# Tension-Logger_Rev_A.net
KiCad netlist of a schematic drawn in EAGLE
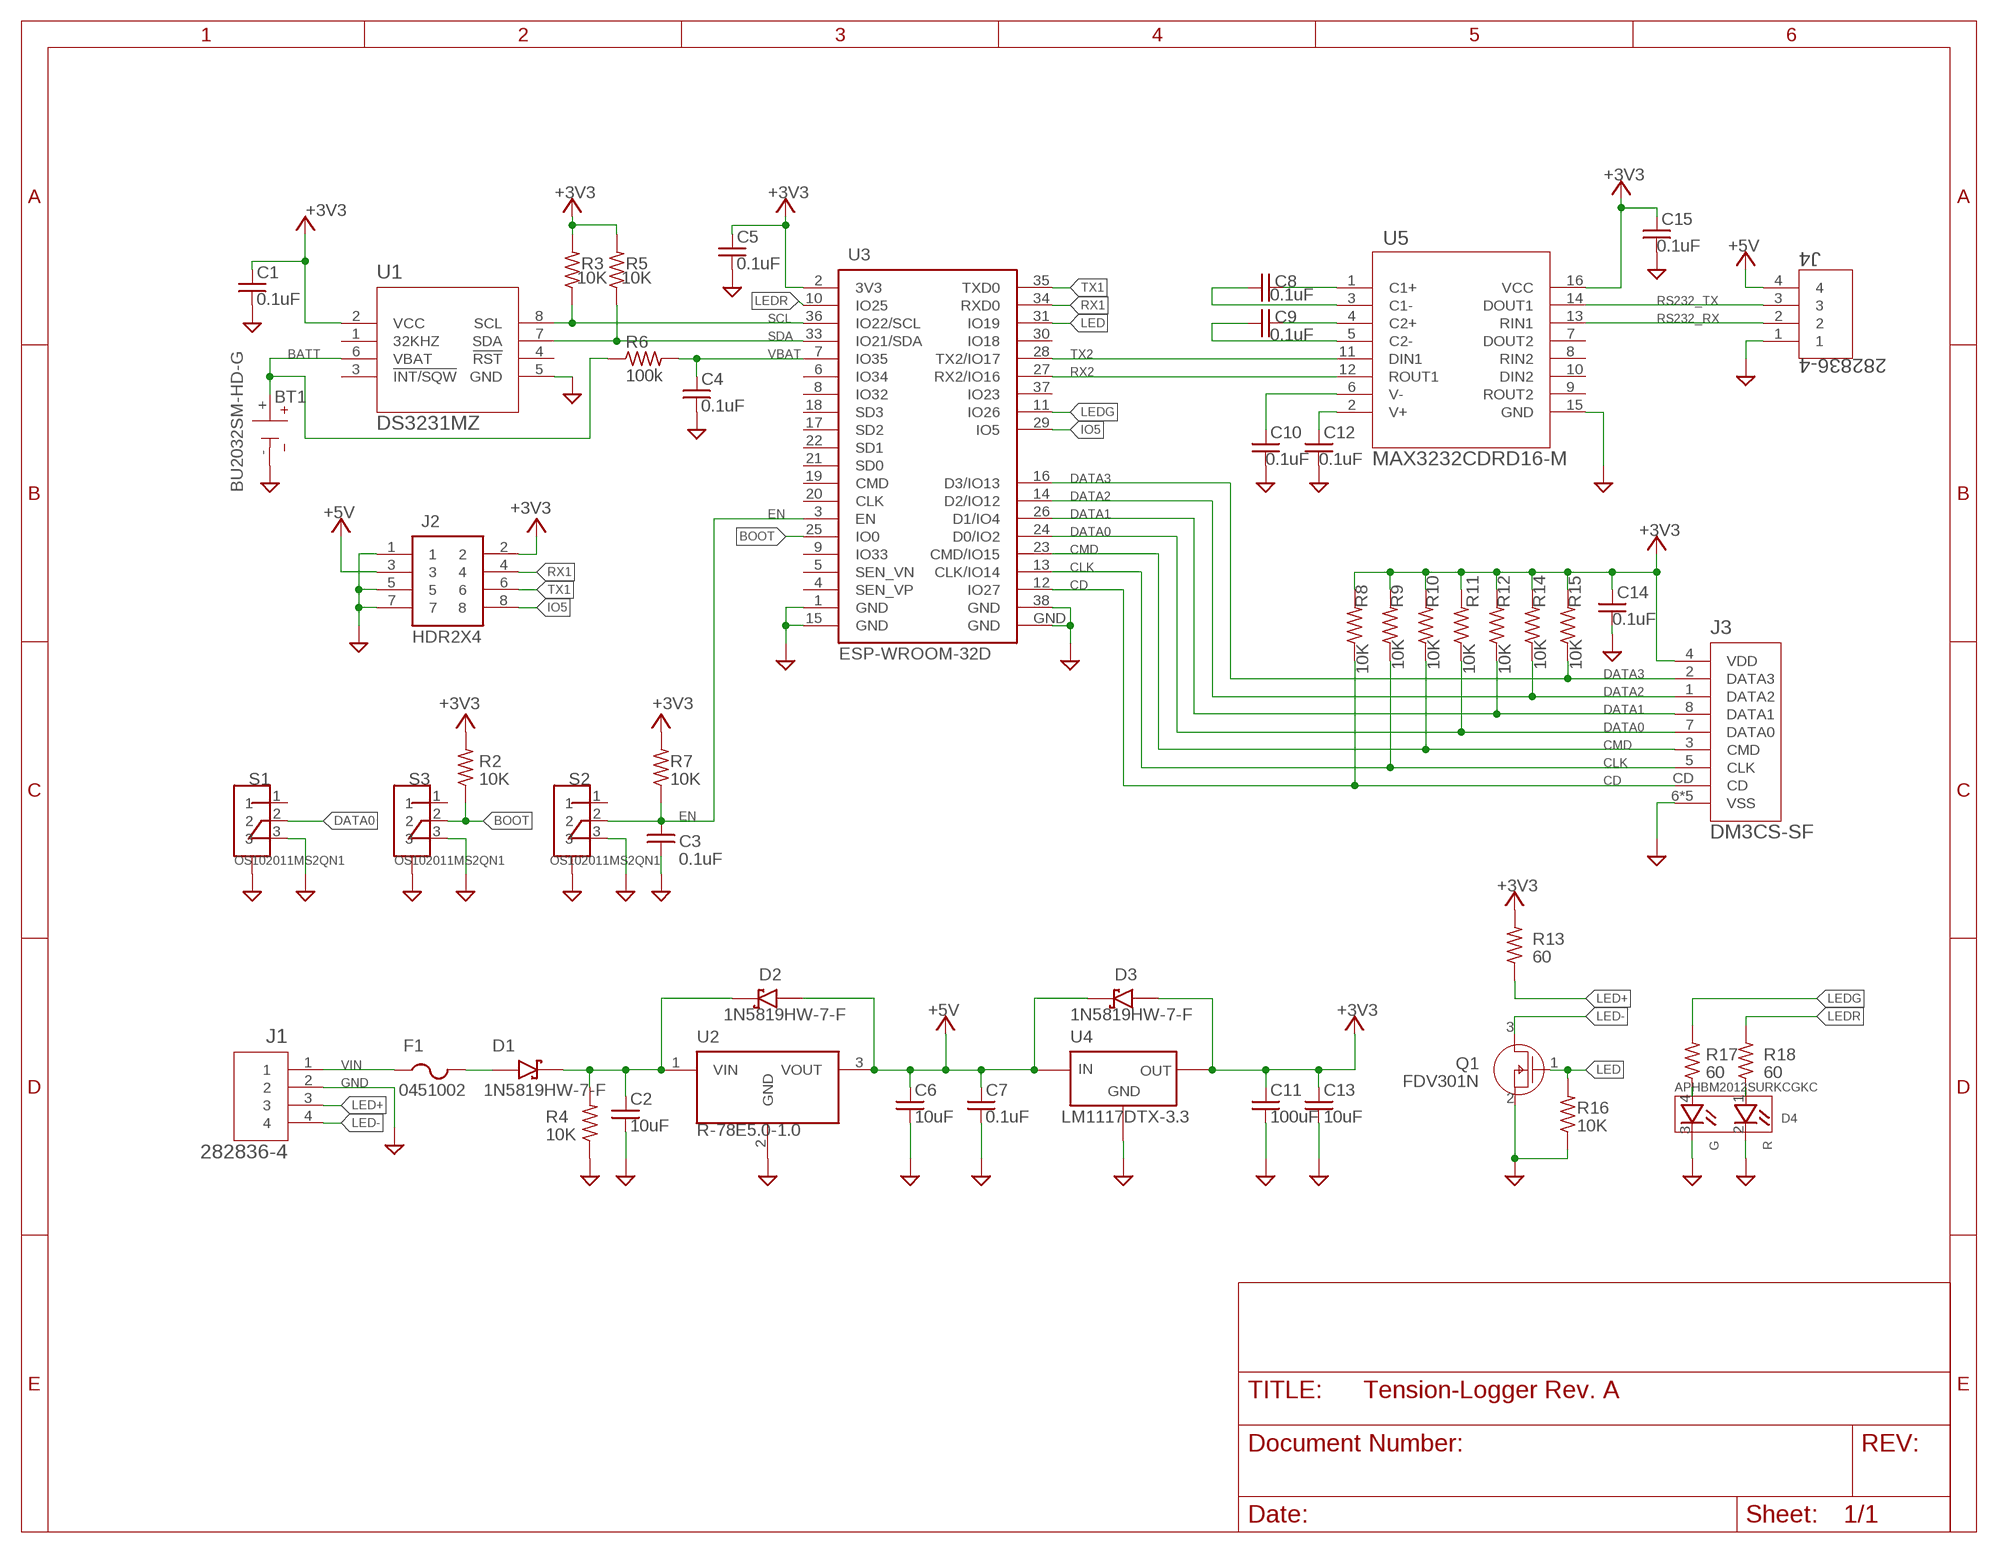
[diagram p0: schematic, sheet 1]

(export (version "E")
  (design (tool "Eeschema 10.0.6"))
  (components
    (comp (ref "BT1")
      (value "BU2032SM-HD-G")
      (footprint "eagle-import:BAT_BU2032SM-HD-G")
      (fields (field (name "MF") "MPD (Memory Protection Devices)"))
      (libsource (lib "eagle-import") (part "BU2032SM-HD-G"))
    )
    (comp (ref "C1")
      (value "0.1uF")
      (footprint "eagle-import:0805")
      (libsource (lib "eagle-import") (part "C0805"))
    )
    (comp (ref "C2")
      (value "10uF")
      (footprint "eagle-import:0805")
      (libsource (lib "eagle-import") (part "C0805"))
    )
    (comp (ref "C3")
      (value "0.1uF")
      (footprint "eagle-import:0805")
      (libsource (lib "eagle-import") (part "C0805"))
    )
    (comp (ref "C4")
      (value "0.1uF")
      (footprint "eagle-import:0805")
      (libsource (lib "eagle-import") (part "C0805"))
    )
    (comp (ref "C5")
      (value "0.1uF")
      (footprint "eagle-import:0805")
      (libsource (lib "eagle-import") (part "C0805"))
    )
    (comp (ref "C6")
      (value "10uF")
      (footprint "eagle-import:0805")
      (libsource (lib "eagle-import") (part "C0805"))
    )
    (comp (ref "C7")
      (value "0.1uF")
      (footprint "eagle-import:0805")
      (libsource (lib "eagle-import") (part "C0805"))
    )
    (comp (ref "C8")
      (value "0.1uF")
      (footprint "eagle-import:0805")
      (libsource (lib "eagle-import") (part "C0805"))
    )
    (comp (ref "C9")
      (value "0.1uF")
      (footprint "eagle-import:0805")
      (libsource (lib "eagle-import") (part "C0805"))
    )
    (comp (ref "C10")
      (value "0.1uF")
      (footprint "eagle-import:0805")
      (libsource (lib "eagle-import") (part "C0805"))
    )
    (comp (ref "C11")
      (value "100uF")
      (footprint "eagle-import:1210")
      (libsource (lib "eagle-import") (part "C1210"))
    )
    (comp (ref "C12")
      (value "0.1uF")
      (footprint "eagle-import:0805")
      (libsource (lib "eagle-import") (part "C0805"))
    )
    (comp (ref "C13")
      (value "10uF")
      (footprint "eagle-import:1210")
      (libsource (lib "eagle-import") (part "C1210"))
    )
    (comp (ref "C14")
      (value "0.1uF")
      (footprint "eagle-import:0805")
      (libsource (lib "eagle-import") (part "C0805"))
    )
    (comp (ref "C15")
      (value "0.1uF")
      (footprint "eagle-import:0805")
      (libsource (lib "eagle-import") (part "C0805"))
    )
    (comp (ref "D1")
      (value "1N5819HW-7-F")
      (footprint "eagle-import:SOD3715X145N")
      (fields (field (name "DIGI-KEY_PART_NUMBER") "1N5819HW-FDICT-ND") (field (name "MF") "Diodes Inc."))
      (libsource (lib "eagle-import") (part "1N5819HW-7-F"))
    )
    (comp (ref "D2")
      (value "1N5819HW-7-F")
      (footprint "eagle-import:SOD3715X145N")
      (fields (field (name "DIGI-KEY_PART_NUMBER") "1N5819HW-FDICT-ND") (field (name "MF") "Diodes Inc."))
      (libsource (lib "eagle-import") (part "1N5819HW-7-F"))
    )
    (comp (ref "D3")
      (value "1N5819HW-7-F")
      (footprint "eagle-import:SOD3715X145N")
      (fields (field (name "DIGI-KEY_PART_NUMBER") "1N5819HW-FDICT-ND") (field (name "MF") "Diodes Inc."))
      (libsource (lib "eagle-import") (part "1N5819HW-7-F"))
    )
    (comp (ref "D4")
      (value "APHBM2012SURKCGKC")
      (footprint "eagle-import:LED_APHBM2012SURKCGKC")
      (fields (field (name "DIGI-KEY_PART_NUMBER") "754-1093-1-ND") (field (name "MF") "Kingbright"))
      (libsource (lib "eagle-import") (part "APHBM2012SURKCGKC"))
    )
    (comp (ref "F1")
      (value "0451002")
      (footprint "eagle-import:FUSC6131X270")
      (libsource (lib "eagle-import") (part "0451002_MRL6.1_2.69_2.69MM"))
    )
    (comp (ref "J1")
      (value "282836-4")
      (footprint "eagle-import:282836-4_TYC")
      (libsource (lib "eagle-import") (part "282836-4"))
    )
    (comp (ref "J2")
      (value "HDR2X4")
      (footprint "eagle-import:HDR2X4")
      (libsource (lib "eagle-import") (part "HDR2X4"))
    )
    (comp (ref "J3")
      (value "DM3CS-SF")
      (footprint "eagle-import:CONN_3CS-SF")
      (fields (field (name "COPYRIGHT") "Copyright (C) 2018 Accelerated Designs. All rights reserved"))
      (libsource (lib "eagle-import") (part "DM3CS-SF"))
    )
    (comp (ref "J4")
      (value "282836-4")
      (footprint "eagle-import:282836-4_TYC")
      (libsource (lib "eagle-import") (part "282836-4"))
    )
    (comp (ref "Q1")
      (value "FDV301N")
      (footprint "eagle-import:SOT23-3_ONS")
      (fields (field (name "COPYRIGHT") "Copyright (C) 2018 Accelerated Designs. All rights reserved"))
      (libsource (lib "eagle-import") (part "FDV301N"))
    )
    (comp (ref "R2")
      (value "10K")
      (footprint "eagle-import:R0805")
      (libsource (lib "eagle-import") (part "R-US_R0805"))
    )
    (comp (ref "R3")
      (value "10K")
      (footprint "eagle-import:R0805")
      (libsource (lib "eagle-import") (part "R-US_R0805"))
    )
    (comp (ref "R4")
      (value "10K")
      (footprint "eagle-import:R0805")
      (libsource (lib "eagle-import") (part "R-US_R0805"))
    )
    (comp (ref "R5")
      (value "10K")
      (footprint "eagle-import:R0805")
      (libsource (lib "eagle-import") (part "R-US_R0805"))
    )
    (comp (ref "R6")
      (value "100k")
      (footprint "eagle-import:R0805")
      (libsource (lib "eagle-import") (part "R-US_R0805"))
    )
    (comp (ref "R7")
      (value "10K")
      (footprint "eagle-import:R0805")
      (libsource (lib "eagle-import") (part "R-US_R0805"))
    )
    (comp (ref "R8")
      (value "10K")
      (footprint "eagle-import:R0805")
      (libsource (lib "eagle-import") (part "R-US_R0805"))
    )
    (comp (ref "R9")
      (value "10K")
      (footprint "eagle-import:R0805")
      (libsource (lib "eagle-import") (part "R-US_R0805"))
    )
    (comp (ref "R10")
      (value "10K")
      (footprint "eagle-import:R0805")
      (libsource (lib "eagle-import") (part "R-US_R0805"))
    )
    (comp (ref "R11")
      (value "10K")
      (footprint "eagle-import:R0805")
      (libsource (lib "eagle-import") (part "R-US_R0805"))
    )
    (comp (ref "R12")
      (value "10K")
      (footprint "eagle-import:R0805")
      (libsource (lib "eagle-import") (part "R-US_R0805"))
    )
    (comp (ref "R13")
      (value "60")
      (footprint "eagle-import:R0805")
      (libsource (lib "eagle-import") (part "R-US_R0805"))
    )
    (comp (ref "R14")
      (value "10K")
      (footprint "eagle-import:R0805")
      (libsource (lib "eagle-import") (part "R-US_R0805"))
    )
    (comp (ref "R15")
      (value "10K")
      (footprint "eagle-import:R0805")
      (libsource (lib "eagle-import") (part "R-US_R0805"))
    )
    (comp (ref "R16")
      (value "10K")
      (footprint "eagle-import:R0805")
      (libsource (lib "eagle-import") (part "R-US_R0805"))
    )
    (comp (ref "R17")
      (value "60")
      (footprint "eagle-import:R0805")
      (libsource (lib "eagle-import") (part "R-US_R0805"))
    )
    (comp (ref "R18")
      (value "60")
      (footprint "eagle-import:R0805")
      (libsource (lib "eagle-import") (part "R-US_R0805"))
    )
    (comp (ref "S1")
      (value "OS102011MS2QN1")
      (footprint "eagle-import:SW_OS102011MS2QN1")
      (fields (field (name "DIGI-KEY_PART_NUMBER") "CKN12284-ND") (field (name "MF") "C&K"))
      (libsource (lib "eagle-import") (part "OS102011MS2QN1"))
    )
    (comp (ref "S2")
      (value "OS102011MS2QN1")
      (footprint "eagle-import:SW_OS102011MS2QN1")
      (fields (field (name "DIGI-KEY_PART_NUMBER") "CKN12284-ND") (field (name "MF") "C&K"))
      (libsource (lib "eagle-import") (part "OS102011MS2QN1"))
    )
    (comp (ref "S3")
      (value "OS102011MS2QN1")
      (footprint "eagle-import:SW_OS102011MS2QN1")
      (fields (field (name "DIGI-KEY_PART_NUMBER") "CKN12284-ND") (field (name "MF") "C&K"))
      (libsource (lib "eagle-import") (part "OS102011MS2QN1"))
    )
    (comp (ref "U1")
      (value "DS3231MZ")
      (footprint "eagle-import:21-0041B_8_MXM-M")
      (fields (field (name "MANUFACTURER_PART_NUMBER") "DS3231MZ+"))
      (libsource (lib "eagle-import") (part "DS3231MZ+21-0041B_8_MXM-M"))
    )
    (comp (ref "U2")
      (value "R-78E5.0-1.0")
      (footprint "eagle-import:CONV_R-78E5.0-1.0")
      (fields (field (name "DIGI-KEY_PART_NUMBER") "945-2201-ND") (field (name "MF") "Recom Power"))
      (libsource (lib "eagle-import") (part "R-78E5.0-1.0"))
    )
    (comp (ref "U3")
      (value "ESP-WROOM-32D")
      (footprint "eagle-import:ESP-WROOM-32")
      (libsource (lib "eagle-import") (part "ESP-WROOM-32"))
    )
    (comp (ref "U4")
      (value "LM1117DTX-3.3")
      (footprint "eagle-import:TO252")
      (libsource (lib "eagle-import") (part "LM1117DTX-3.3"))
    )
    (comp (ref "U5")
      (value "MAX3232CDRD16-M")
      (footprint "eagle-import:D16-M")
      (fields (field (name "MANUFACTURER_PART_NUMBER") "MAX3232CDR"))
      (libsource (lib "eagle-import") (part "MAX3232CDRD16-M"))
    )
  )
  (nets
    (net (code "1") (name "+3V3") (class "Default")
      (node (ref "C1") (pin "B") (pinfunction "2_B") (pintype "passive"))
      (node (ref "C11") (pin "A") (pinfunction "1_A") (pintype "passive"))
      (node (ref "C13") (pin "A") (pinfunction "1_A") (pintype "passive"))
      (node (ref "C14") (pin "A") (pinfunction "1_A") (pintype "passive"))
      (node (ref "C15") (pin "B") (pinfunction "2_B") (pintype "passive"))
      (node (ref "C5") (pin "B") (pinfunction "2_B") (pintype "passive"))
      (node (ref "D3") (pin "A") (pinfunction "A_A") (pintype "passive"))
      (node (ref "J2") (pin "2") (pinfunction "2_2") (pintype "bidirectional"))
      (node (ref "J3") (pin "4") (pinfunction "VDD_4") (pintype "passive"))
      (node (ref "R10") (pin "2") (pinfunction "2_2") (pintype "passive"))
      (node (ref "R11") (pin "2") (pinfunction "2_2") (pintype "passive"))
      (node (ref "R12") (pin "2") (pinfunction "2_2") (pintype "passive"))
      (node (ref "R13") (pin "2") (pinfunction "2_2") (pintype "passive"))
      (node (ref "R14") (pin "2") (pinfunction "2_2") (pintype "passive"))
      (node (ref "R15") (pin "2") (pinfunction "2_2") (pintype "passive"))
      (node (ref "R2") (pin "2") (pinfunction "2_2") (pintype "passive"))
      (node (ref "R3") (pin "2") (pinfunction "2_2") (pintype "passive"))
      (node (ref "R5") (pin "2") (pinfunction "2_2") (pintype "passive"))
      (node (ref "R7") (pin "2") (pinfunction "2_2") (pintype "passive"))
      (node (ref "R8") (pin "2") (pinfunction "2_2") (pintype "passive"))
      (node (ref "R9") (pin "2") (pinfunction "2_2") (pintype "passive"))
      (node (ref "U1") (pin "2") (pinfunction "VCC_2") (pintype "power_in"))
      (node (ref "U3") (pin "2") (pinfunction "3V3_2") (pintype "power_in"))
      (node (ref "U4") (pin "TAB") (pinfunction "OUT_TAB") (pintype "passive"))
      (node (ref "U5") (pin "16") (pinfunction "VCC_16") (pintype "power_in"))
    )
    (net (code "2") (name "+5V") (class "Default")
      (node (ref "C6") (pin "A") (pinfunction "1_A") (pintype "passive"))
      (node (ref "C7") (pin "A") (pinfunction "1_A") (pintype "passive"))
      (node (ref "D2") (pin "A") (pinfunction "A_A") (pintype "passive"))
      (node (ref "D3") (pin "C") (pinfunction "K_C") (pintype "passive"))
      (node (ref "J2") (pin "3") (pinfunction "3_3") (pintype "bidirectional"))
      (node (ref "J4") (pin "4") (pinfunction "4_4") (pintype "passive"))
      (node (ref "U2") (pin "3") (pinfunction "VOUT_3") (pintype "output"))
      (node (ref "U4") (pin "2") (pinfunction "IN_2") (pintype "input"))
    )
    (net (code "3") (name "/BATT") (class "Default")
      (node (ref "BT1") (pin "+") (pinfunction "+_+") (pintype "passive"))
      (node (ref "R6") (pin "1") (pinfunction "1_1") (pintype "passive"))
      (node (ref "U1") (pin "6") (pinfunction "VBAT_6") (pintype "power_in"))
    )
    (net (code "4") (name "/CD") (class "Default")
      (node (ref "J3") (pin "CD") (pinfunction "CD_CD") (pintype "bidirectional"))
      (node (ref "R8") (pin "1") (pinfunction "1_1") (pintype "passive"))
      (node (ref "U3") (pin "12") (pinfunction "IO27_12") (pintype "bidirectional"))
    )
    (net (code "5") (name "/CLK") (class "Default")
      (node (ref "J3") (pin "5") (pinfunction "CLK_5") (pintype "passive"))
      (node (ref "R9") (pin "1") (pinfunction "1_1") (pintype "passive"))
      (node (ref "U3") (pin "13") (pinfunction "CLK/IO14_13") (pintype "bidirectional"))
    )
    (net (code "6") (name "/CMD") (class "Default")
      (node (ref "J3") (pin "3") (pinfunction "CMD_3") (pintype "passive"))
      (node (ref "R10") (pin "1") (pinfunction "1_1") (pintype "passive"))
      (node (ref "U3") (pin "23") (pinfunction "CMD/IO15_23") (pintype "bidirectional"))
    )
    (net (code "7") (name "/DATA1") (class "Default")
      (node (ref "J3") (pin "8") (pinfunction "DATA1_8") (pintype "passive"))
      (node (ref "R12") (pin "1") (pinfunction "1_1") (pintype "passive"))
      (node (ref "U3") (pin "26") (pinfunction "D1/IO4_26") (pintype "bidirectional"))
    )
    (net (code "8") (name "/DATA2") (class "Default")
      (node (ref "J3") (pin "1") (pinfunction "DATA2_1") (pintype "passive"))
      (node (ref "R14") (pin "1") (pinfunction "1_1") (pintype "passive"))
      (node (ref "U3") (pin "14") (pinfunction "D2/IO12_14") (pintype "bidirectional"))
    )
    (net (code "9") (name "/DATA3") (class "Default")
      (node (ref "J3") (pin "2") (pinfunction "DATA3_2") (pintype "passive"))
      (node (ref "R15") (pin "1") (pinfunction "1_1") (pintype "passive"))
      (node (ref "U3") (pin "16") (pinfunction "D3/IO13_16") (pintype "bidirectional"))
    )
    (net (code "10") (name "/EN") (class "Default")
      (node (ref "C3") (pin "B") (pinfunction "2_B") (pintype "passive"))
      (node (ref "R7") (pin "1") (pinfunction "1_1") (pintype "passive"))
      (node (ref "S2") (pin "2") (pinfunction "2_2") (pintype "passive"))
      (node (ref "U3") (pin "3") (pinfunction "EN_3") (pintype "input"))
    )
    (net (code "11") (name "/RS232_RX") (class "Default")
      (node (ref "J4") (pin "2") (pinfunction "2_2") (pintype "passive"))
      (node (ref "U5") (pin "13") (pinfunction "RIN1_13") (pintype "input"))
    )
    (net (code "12") (name "/RS232_TX") (class "Default")
      (node (ref "J4") (pin "3") (pinfunction "3_3") (pintype "passive"))
      (node (ref "U5") (pin "14") (pinfunction "DOUT1_14") (pintype "output"))
    )
    (net (code "13") (name "/RX2") (class "Default")
      (node (ref "U3") (pin "27") (pinfunction "RX2/IO16_27") (pintype "bidirectional"))
      (node (ref "U5") (pin "12") (pinfunction "ROUT1_12") (pintype "output"))
    )
    (net (code "14") (name "/SCL") (class "Default")
      (node (ref "R3") (pin "1") (pinfunction "1_1") (pintype "passive"))
      (node (ref "U1") (pin "8") (pinfunction "SCL_8") (pintype "input"))
      (node (ref "U3") (pin "36") (pinfunction "IO22/SCL_36") (pintype "bidirectional"))
    )
    (net (code "15") (name "/SDA") (class "Default")
      (node (ref "R5") (pin "1") (pinfunction "1_1") (pintype "passive"))
      (node (ref "U1") (pin "7") (pinfunction "SDA_7") (pintype "passive"))
      (node (ref "U3") (pin "33") (pinfunction "IO21/SDA_33") (pintype "bidirectional"))
    )
    (net (code "16") (name "/TX2") (class "Default")
      (node (ref "U3") (pin "28") (pinfunction "TX2/IO17_28") (pintype "bidirectional"))
      (node (ref "U5") (pin "11") (pinfunction "DIN1_11") (pintype "input"))
    )
    (net (code "17") (name "/VBAT") (class "Default")
      (node (ref "C4") (pin "B") (pinfunction "2_B") (pintype "passive"))
      (node (ref "R6") (pin "2") (pinfunction "2_2") (pintype "passive"))
      (node (ref "U3") (pin "7") (pinfunction "IO35_7") (pintype "bidirectional"))
    )
    (net (code "18") (name "/VIN") (class "Default")
      (node (ref "F1") (pin "1") (pinfunction "1_1") (pintype "passive"))
      (node (ref "J1") (pin "1") (pinfunction "1_1") (pintype "passive"))
    )
    (net (code "19") (name "BOOT") (class "Default")
      (node (ref "R2") (pin "1") (pinfunction "1_1") (pintype "passive"))
      (node (ref "S3") (pin "2") (pinfunction "2_2") (pintype "passive"))
      (node (ref "U3") (pin "25") (pinfunction "IO0_25") (pintype "bidirectional"))
    )
    (net (code "20") (name "DATA0") (class "Default")
      (node (ref "J3") (pin "7") (pinfunction "DATA0_7") (pintype "passive"))
      (node (ref "R11") (pin "1") (pinfunction "1_1") (pintype "passive"))
      (node (ref "S1") (pin "2") (pinfunction "2_2") (pintype "passive"))
      (node (ref "U3") (pin "24") (pinfunction "D0/IO2_24") (pintype "bidirectional"))
    )
    (net (code "21") (name "GND") (class "Default")
      (node (ref "BT1") (pin "-") (pinfunction "-_-") (pintype "passive"))
      (node (ref "C1") (pin "A") (pinfunction "1_A") (pintype "passive"))
      (node (ref "C10") (pin "B") (pinfunction "2_B") (pintype "passive"))
      (node (ref "C11") (pin "B") (pinfunction "2_B") (pintype "passive"))
      (node (ref "C12") (pin "B") (pinfunction "2_B") (pintype "passive"))
      (node (ref "C13") (pin "B") (pinfunction "2_B") (pintype "passive"))
      (node (ref "C14") (pin "B") (pinfunction "2_B") (pintype "passive"))
      (node (ref "C15") (pin "A") (pinfunction "1_A") (pintype "passive"))
      (node (ref "C2") (pin "B") (pinfunction "2_B") (pintype "passive"))
      (node (ref "C3") (pin "A") (pinfunction "1_A") (pintype "passive"))
      (node (ref "C4") (pin "A") (pinfunction "1_A") (pintype "passive"))
      (node (ref "C5") (pin "A") (pinfunction "1_A") (pintype "passive"))
      (node (ref "C6") (pin "B") (pinfunction "2_B") (pintype "passive"))
      (node (ref "C7") (pin "B") (pinfunction "2_B") (pintype "passive"))
      (node (ref "D4") (pin "2") (pinfunction "C_R_2") (pintype "passive"))
      (node (ref "D4") (pin "3") (pinfunction "C_G_3") (pintype "passive"))
      (node (ref "J1") (pin "2") (pinfunction "2_2") (pintype "passive"))
      (node (ref "J2") (pin "1") (pinfunction "1_1") (pintype "bidirectional"))
      (node (ref "J2") (pin "5") (pinfunction "5_5") (pintype "bidirectional"))
      (node (ref "J2") (pin "7") (pinfunction "7_7") (pintype "bidirectional"))
      (node (ref "J3") (pin "6") (pinfunction "VSS_6") (pintype "passive"))
      (node (ref "J3") (pin "GND-1") (pinfunction "VSS_GND-1") (pintype "passive"))
      (node (ref "J3") (pin "GND-2") (pinfunction "VSS_GND-2") (pintype "passive"))
      (node (ref "J3") (pin "GND-3") (pinfunction "VSS_GND-3") (pintype "passive"))
      (node (ref "J3") (pin "GND-4") (pinfunction "VSS_GND-4") (pintype "passive"))
      (node (ref "J4") (pin "1") (pinfunction "1_1") (pintype "passive"))
      (node (ref "Q1") (pin "2") (pinfunction "S_2") (pintype "passive"))
      (node (ref "R16") (pin "1") (pinfunction "1_1") (pintype "passive"))
      (node (ref "R4") (pin "1") (pinfunction "1_1") (pintype "passive"))
      (node (ref "S1") (pin "3") (pinfunction "3_3") (pintype "passive"))
      (node (ref "S1") (pin "M1") (pinfunction "CASE_M1") (pintype "bidirectional"))
      (node (ref "S1") (pin "M2") (pinfunction "CASE_M2") (pintype "bidirectional"))
      (node (ref "S2") (pin "3") (pinfunction "3_3") (pintype "passive"))
      (node (ref "S2") (pin "M1") (pinfunction "CASE_M1") (pintype "bidirectional"))
      (node (ref "S2") (pin "M2") (pinfunction "CASE_M2") (pintype "bidirectional"))
      (node (ref "S3") (pin "3") (pinfunction "3_3") (pintype "passive"))
      (node (ref "S3") (pin "M1") (pinfunction "CASE_M1") (pintype "bidirectional"))
      (node (ref "S3") (pin "M2") (pinfunction "CASE_M2") (pintype "bidirectional"))
      (node (ref "U1") (pin "5") (pinfunction "GND_5") (pintype "power_in"))
      (node (ref "U2") (pin "2") (pinfunction "GND_2") (pintype "power_in"))
      (node (ref "U3") (pin "1") (pinfunction "GND_1") (pintype "power_in"))
      (node (ref "U3") (pin "15") (pinfunction "GND_15") (pintype "power_in"))
      (node (ref "U3") (pin "38") (pinfunction "GND_38") (pintype "power_in"))
      (node (ref "U3") (pin "GND") (pinfunction "GND_GND") (pintype "power_in"))
      (node (ref "U4") (pin "1") (pinfunction "GND_1") (pintype "input"))
      (node (ref "U5") (pin "15") (pinfunction "GND_15") (pintype "power_in"))
    )
    (net (code "22") (name "IO5") (class "Default")
      (node (ref "J2") (pin "8") (pinfunction "8_8") (pintype "bidirectional"))
      (node (ref "U3") (pin "29") (pinfunction "IO5_29") (pintype "bidirectional"))
    )
    (net (code "23") (name "LED") (class "Default")
      (node (ref "Q1") (pin "1") (pinfunction "G_1") (pintype "passive"))
      (node (ref "R16") (pin "2") (pinfunction "2_2") (pintype "passive"))
      (node (ref "U3") (pin "31") (pinfunction "IO19_31") (pintype "bidirectional"))
    )
    (net (code "24") (name "LED+") (class "Default")
      (node (ref "J1") (pin "3") (pinfunction "3_3") (pintype "passive"))
      (node (ref "R13") (pin "1") (pinfunction "1_1") (pintype "passive"))
    )
    (net (code "25") (name "LED-") (class "Default")
      (node (ref "J1") (pin "4") (pinfunction "4_4") (pintype "passive"))
      (node (ref "Q1") (pin "3") (pinfunction "D_3") (pintype "passive"))
    )
    (net (code "26") (name "LEDG") (class "Default")
      (node (ref "R17") (pin "2") (pinfunction "2_2") (pintype "passive"))
      (node (ref "U3") (pin "11") (pinfunction "IO26_11") (pintype "bidirectional"))
    )
    (net (code "27") (name "LEDR") (class "Default")
      (node (ref "R18") (pin "2") (pinfunction "2_2") (pintype "passive"))
      (node (ref "U3") (pin "10") (pinfunction "IO25_10") (pintype "bidirectional"))
    )
    (net (code "28") (name "Net-(C2-1)") (class "Default")
      (node (ref "C2") (pin "A") (pinfunction "1_A") (pintype "passive"))
      (node (ref "D1") (pin "C") (pinfunction "K_C") (pintype "passive"))
      (node (ref "D2") (pin "C") (pinfunction "K_C") (pintype "passive"))
      (node (ref "R4") (pin "2") (pinfunction "2_2") (pintype "passive"))
      (node (ref "U2") (pin "1") (pinfunction "VIN_1") (pintype "input"))
    )
    (net (code "29") (name "Net-(C8-1)") (class "Default")
      (node (ref "C8") (pin "A") (pinfunction "1_A") (pintype "passive"))
      (node (ref "U5") (pin "3") (pinfunction "C1-_3") (pintype "passive"))
    )
    (net (code "30") (name "Net-(C8-2)") (class "Default")
      (node (ref "C8") (pin "B") (pinfunction "2_B") (pintype "passive"))
      (node (ref "U5") (pin "1") (pinfunction "C1+_1") (pintype "passive"))
    )
    (net (code "31") (name "Net-(C9-1)") (class "Default")
      (node (ref "C9") (pin "A") (pinfunction "1_A") (pintype "passive"))
      (node (ref "U5") (pin "5") (pinfunction "C2-_5") (pintype "passive"))
    )
    (net (code "32") (name "Net-(C9-2)") (class "Default")
      (node (ref "C9") (pin "B") (pinfunction "2_B") (pintype "passive"))
      (node (ref "U5") (pin "4") (pinfunction "C2+_4") (pintype "passive"))
    )
    (net (code "33") (name "Net-(C10-1)") (class "Default")
      (node (ref "C10") (pin "A") (pinfunction "1_A") (pintype "passive"))
      (node (ref "U5") (pin "6") (pinfunction "V-_6") (pintype "power_in"))
    )
    (net (code "34") (name "Net-(C12-1)") (class "Default")
      (node (ref "C12") (pin "A") (pinfunction "1_A") (pintype "passive"))
      (node (ref "U5") (pin "2") (pinfunction "V+_2") (pintype "power_in"))
    )
    (net (code "35") (name "Net-(D1-PadA)") (class "Default")
      (node (ref "D1") (pin "A") (pinfunction "A_A") (pintype "passive"))
      (node (ref "F1") (pin "2") (pinfunction "2_2") (pintype "passive"))
    )
    (net (code "36") (name "Net-(D4-A_G)") (class "Default")
      (node (ref "D4") (pin "4") (pinfunction "A_G_4") (pintype "passive"))
      (node (ref "R17") (pin "1") (pinfunction "1_1") (pintype "passive"))
    )
    (net (code "37") (name "Net-(D4-A_R)") (class "Default")
      (node (ref "D4") (pin "1") (pinfunction "A_R_1") (pintype "passive"))
      (node (ref "R18") (pin "1") (pinfunction "1_1") (pintype "passive"))
    )
    (net (code "38") (name "RX1") (class "Default")
      (node (ref "J2") (pin "4") (pinfunction "4_4") (pintype "bidirectional"))
      (node (ref "U3") (pin "34") (pinfunction "RXD0_34") (pintype "bidirectional"))
    )
    (net (code "39") (name "TX1") (class "Default")
      (node (ref "J2") (pin "6") (pinfunction "6_6") (pintype "bidirectional"))
      (node (ref "U3") (pin "35") (pinfunction "TXD0_35") (pintype "bidirectional"))
    )
    (net (code "40") (name "unconnected-(S1-Pad1)") (class "Default")
      (node (ref "S1") (pin "1") (pinfunction "1_1") (pintype "passive"))
    )
    (net (code "41") (name "unconnected-(S2-Pad1)") (class "Default")
      (node (ref "S2") (pin "1") (pinfunction "1_1") (pintype "passive"))
    )
    (net (code "42") (name "unconnected-(S3-Pad1)") (class "Default")
      (node (ref "S3") (pin "1") (pinfunction "1_1") (pintype "passive"))
    )
    (net (code "43") (name "unconnected-(U1-32KHZ-Pad1)") (class "Default")
      (node (ref "U1") (pin "1") (pinfunction "32KHZ_1") (pintype "output"))
    )
    (net (code "44") (name "unconnected-(U1-~{INT{slash}SQW}-Pad3)") (class "Default")
      (node (ref "U1") (pin "3") (pinfunction "~{INT/SQW}_3") (pintype "output"))
    )
    (net (code "45") (name "unconnected-(U1-~{RST}-Pad4)") (class "Default")
      (node (ref "U1") (pin "4") (pinfunction "~{RST}_4") (pintype "passive"))
    )
    (net (code "46") (name "unconnected-(U3-CLK-Pad20)") (class "Default")
      (node (ref "U3") (pin "20") (pinfunction "CLK_20") (pintype "bidirectional"))
    )
    (net (code "47") (name "unconnected-(U3-CMD-Pad19)") (class "Default")
      (node (ref "U3") (pin "19") (pinfunction "CMD_19") (pintype "bidirectional"))
    )
    (net (code "48") (name "unconnected-(U3-IO18-Pad30)") (class "Default")
      (node (ref "U3") (pin "30") (pinfunction "IO18_30") (pintype "bidirectional"))
    )
    (net (code "49") (name "unconnected-(U3-IO23-Pad37)") (class "Default")
      (node (ref "U3") (pin "37") (pinfunction "IO23_37") (pintype "bidirectional"))
    )
    (net (code "50") (name "unconnected-(U3-IO32-Pad8)") (class "Default")
      (node (ref "U3") (pin "8") (pinfunction "IO32_8") (pintype "bidirectional"))
    )
    (net (code "51") (name "unconnected-(U3-IO33-Pad9)") (class "Default")
      (node (ref "U3") (pin "9") (pinfunction "IO33_9") (pintype "bidirectional"))
    )
    (net (code "52") (name "unconnected-(U3-IO34-Pad6)") (class "Default")
      (node (ref "U3") (pin "6") (pinfunction "IO34_6") (pintype "bidirectional"))
    )
    (net (code "53") (name "unconnected-(U3-SD0-Pad21)") (class "Default")
      (node (ref "U3") (pin "21") (pinfunction "SD0_21") (pintype "bidirectional"))
    )
    (net (code "54") (name "unconnected-(U3-SD1-Pad22)") (class "Default")
      (node (ref "U3") (pin "22") (pinfunction "SD1_22") (pintype "bidirectional"))
    )
    (net (code "55") (name "unconnected-(U3-SD2-Pad17)") (class "Default")
      (node (ref "U3") (pin "17") (pinfunction "SD2_17") (pintype "bidirectional"))
    )
    (net (code "56") (name "unconnected-(U3-SD3-Pad18)") (class "Default")
      (node (ref "U3") (pin "18") (pinfunction "SD3_18") (pintype "bidirectional"))
    )
    (net (code "57") (name "unconnected-(U3-SEN_VN-Pad5)") (class "Default")
      (node (ref "U3") (pin "5") (pinfunction "SEN_VN_5") (pintype "bidirectional"))
    )
    (net (code "58") (name "unconnected-(U3-SEN_VP-Pad4)") (class "Default")
      (node (ref "U3") (pin "4") (pinfunction "SEN_VP_4") (pintype "bidirectional"))
    )
    (net (code "59") (name "unconnected-(U5-DIN2-Pad10)") (class "Default")
      (node (ref "U5") (pin "10") (pinfunction "DIN2_10") (pintype "input"))
    )
    (net (code "60") (name "unconnected-(U5-DOUT2-Pad7)") (class "Default")
      (node (ref "U5") (pin "7") (pinfunction "DOUT2_7") (pintype "output"))
    )
    (net (code "61") (name "unconnected-(U5-RIN2-Pad8)") (class "Default")
      (node (ref "U5") (pin "8") (pinfunction "RIN2_8") (pintype "input"))
    )
    (net (code "62") (name "unconnected-(U5-ROUT2-Pad9)") (class "Default")
      (node (ref "U5") (pin "9") (pinfunction "ROUT2_9") (pintype "output"))
    )
  )
)
